# Fri3d_2024_Exp0_01.net
KiCad netlist of a schematic drawn in Altium Designer
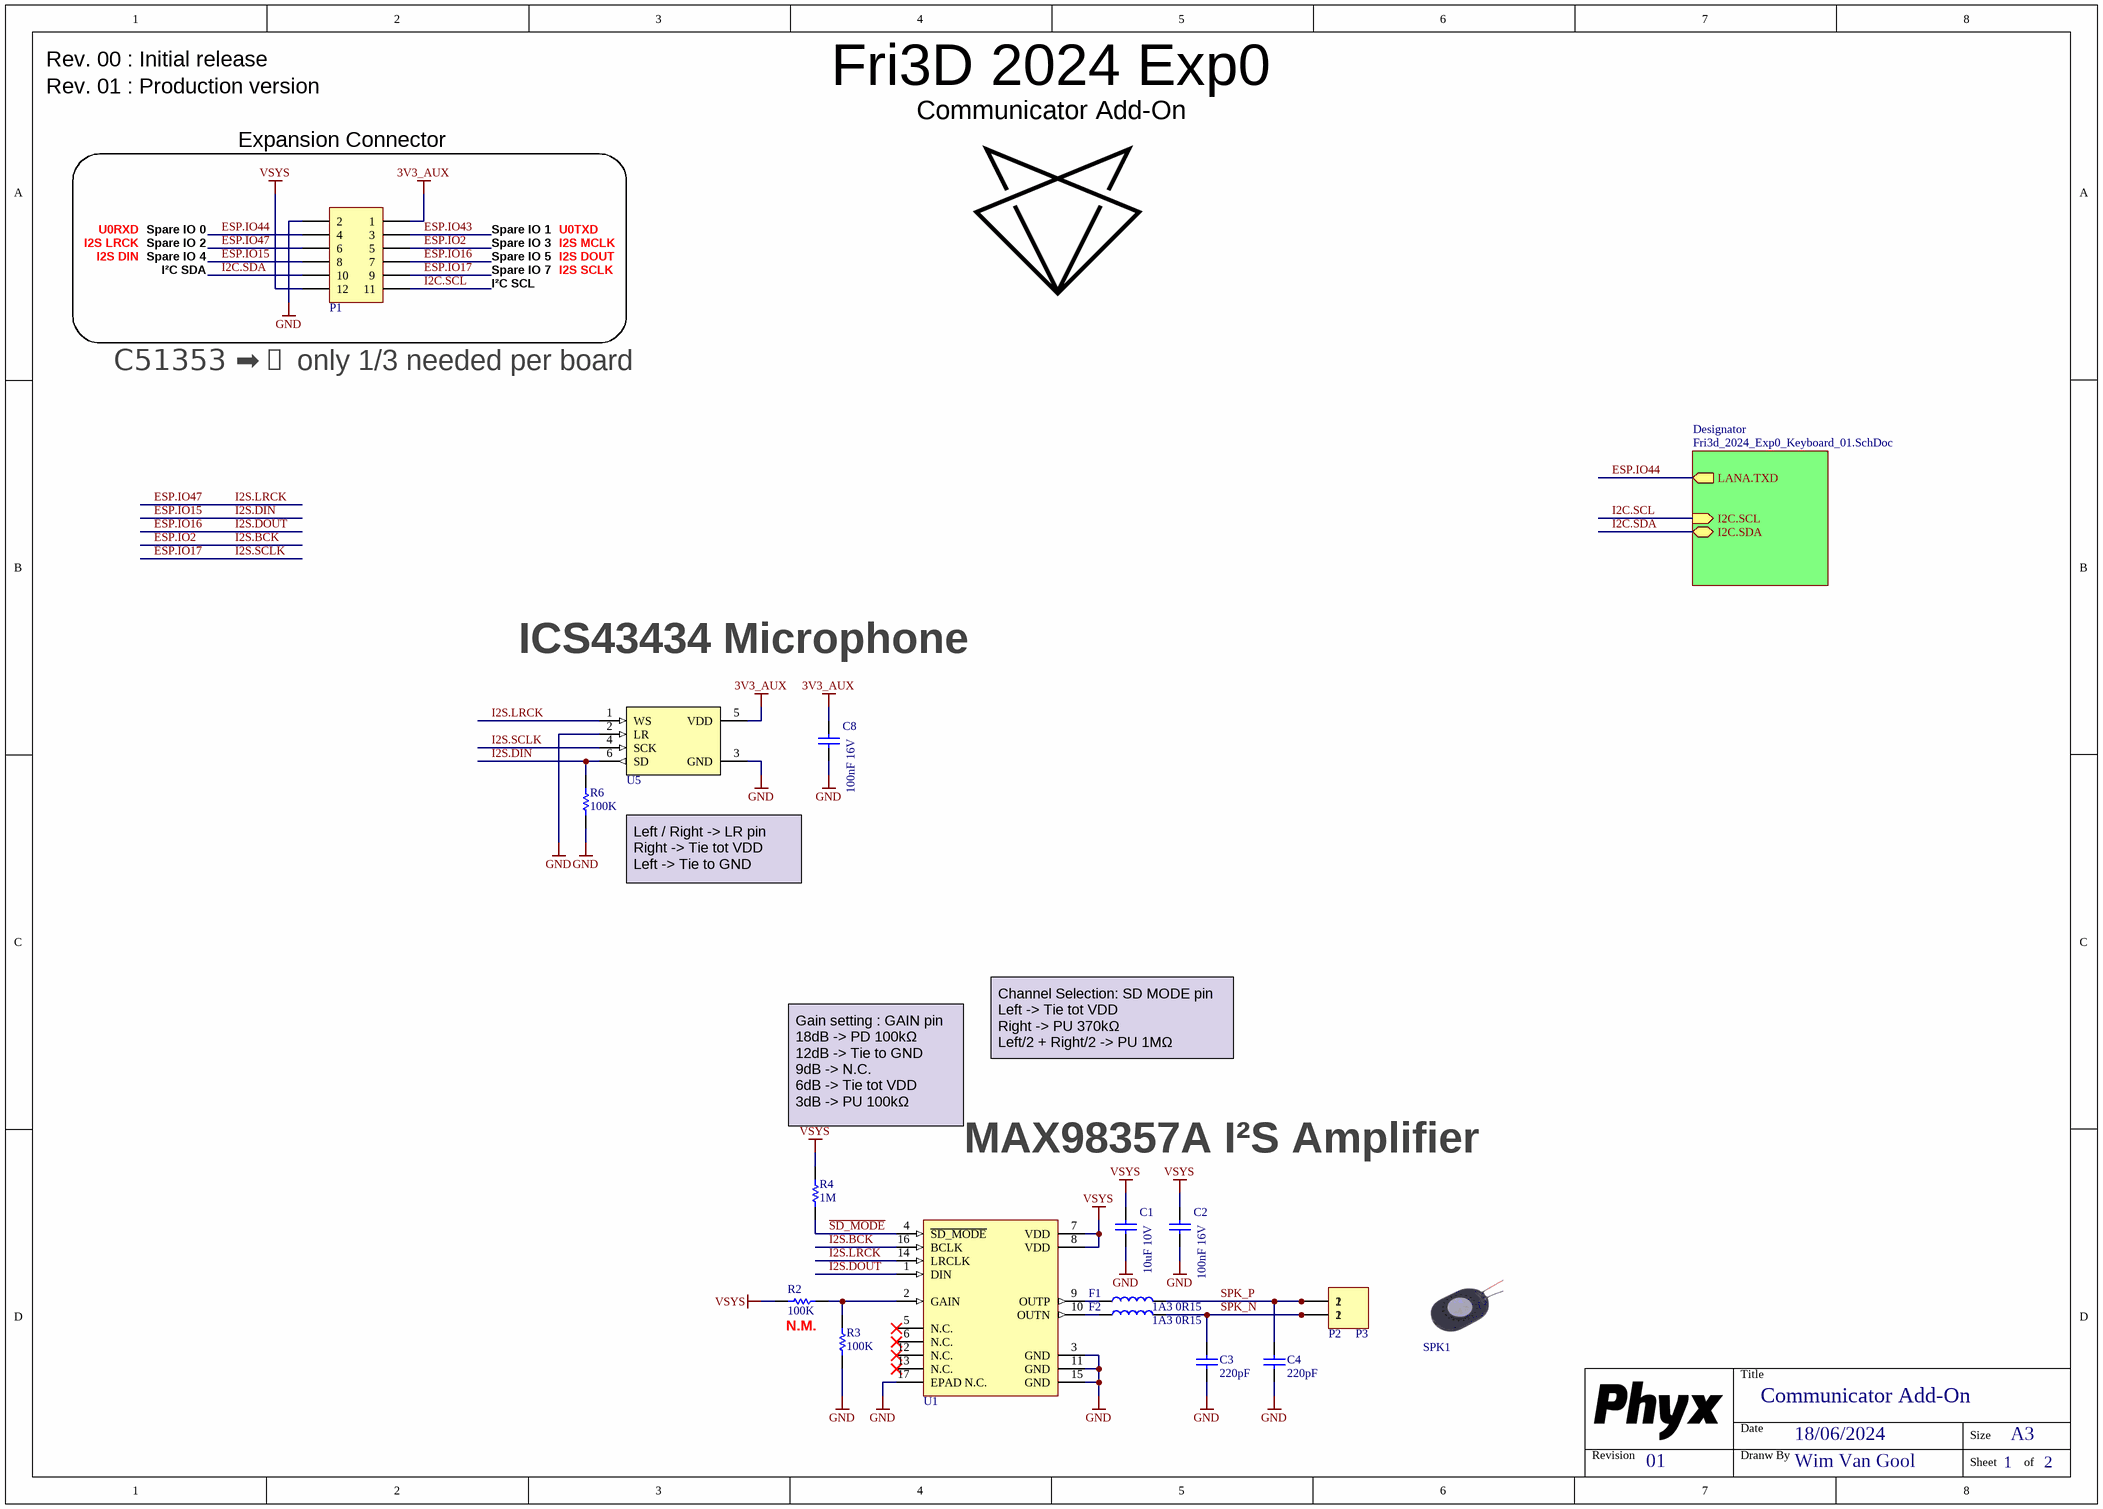
[diagram p0: Fri3d_2024_Exp0_01.SchDoc]

(export (version "E")
  (design (tool "Eeschema 10.0.6"))
  (components
    (comp (ref "C1")
      (value "10uF 10V")
      (footprint "C0805_N")
      (description "Capacitor Ceramic")
      (fields (field (name "Comment") "CAP_CERAMIC"))
      (libsource (lib "Phyx_Components") (part "CAP_CERAMIC"))
    )
    (comp (ref "C2")
      (value "100nF 16V")
      (footprint "C0603_N")
      (description "Capacitor Ceramic")
      (libsource (lib "Phyx_Components") (part "CAP_CERAMIC"))
    )
    (comp (ref "C3")
      (value "220pF")
      (footprint "C0603_N")
      (description "Capacitor Ceramic")
      (fields (field (name "Comment") "CAP_CERAMIC"))
      (libsource (lib "Phyx_Components") (part "CAP_CERAMIC"))
    )
    (comp (ref "C4")
      (value "220pF")
      (footprint "C0603_N")
      (description "Capacitor Ceramic")
      (fields (field (name "Comment") "CAP_CERAMIC"))
      (libsource (lib "Phyx_Components") (part "CAP_CERAMIC"))
    )
    (comp (ref "C8")
      (value "100nF 16V")
      (footprint "C0603_N")
      (description "Capacitor Ceramic")
      (libsource (lib "Phyx_Components") (part "CAP_CERAMIC"))
    )
    (comp (ref "F1")
      (value "1A3 0R15")
      (footprint "L0603")
      (fields (field (name "Comment") "BLM18KG601SN1D"))
      (libsource (lib "Phyx_Components") (part "FERRITE"))
    )
    (comp (ref "F2")
      (value "1A3 0R15")
      (footprint "L0603")
      (fields (field (name "Comment") "BLM18KG601SN1D"))
      (libsource (lib "Phyx_Components") (part "FERRITE"))
    )
    (comp (ref "P1")
      (value "Header 6X2")
      (footprint "HDR2X6")
      (libsource (lib "Phyx_Components") (part "Header 6X2"))
    )
    (comp (ref "P2")
      (value "Header 2.0mm Shrouded 2")
      (footprint "WE_620102131822")
      (libsource (lib "") (part "Header 2_1"))
    )
    (comp (ref "P3")
      (value "Header 2 RA")
      (footprint "HDR1X2_RA")
      (libsource (lib "Phyx_Components") (part "Header 2"))
    )
    (comp (ref "R2")
      (value "100K")
      (footprint "R0603_N")
      (fields (field (name "Comment") "RESISTOR"))
      (libsource (lib "Phyx_Components") (part "RESISTOR"))
    )
    (comp (ref "R3")
      (value "100K")
      (footprint "R0603_N")
      (fields (field (name "Comment") "RESISTOR"))
      (libsource (lib "Phyx_Components") (part "RESISTOR"))
    )
    (comp (ref "R4")
      (value "1M")
      (footprint "R0603_N")
      (fields (field (name "Comment") "RESISTOR"))
      (libsource (lib "Phyx_Components") (part "RESISTOR"))
    )
    (comp (ref "R6")
      (value "100K")
      (footprint "R0603_N")
      (fields (field (name "Comment") "RESISTOR"))
      (libsource (lib "Phyx_Components") (part "RESISTOR"))
    )
    (comp (ref "SPK1")
      (value "INGHAi GSPK3020035PN 8R 1W 100mm Leads")
      (description "SPEAKER 8R 1W 10cm")
      (libsource (lib "Phyx_Components") (part "GSPK3020035PN"))
    )
    (comp (ref "U1")
      (value "Mono I²S DAC AMP 3W 2.5~5.5V")
      (footprint "QFN_16_0.5_3X3")
      (description "=Description")
      (libsource (lib "Phyx_Components") (part "ADI_MAX98357_QFN"))
    )
    (comp (ref "U5")
      (value "I2S MIC ICS-43434")
      (footprint "TDK_ICS-43434")
      (description "=Description")
      (libsource (lib "Phyx_Components") (part "TDK_ICS-43434"))
    )
  )
  (nets
    (net (code "2") (name "/ESP.IO2") (class "Default")
      (node (ref "P1") (pin "5") (pinfunction "5_5") (pintype "passive"))
      (node (ref "U1") (pin "16") (pinfunction "BCLK_16") (pintype "input"))
    )
    (net (code "3") (name "/ESP.IO15") (class "Default")
      (node (ref "P1") (pin "8") (pinfunction "8_8") (pintype "passive"))
      (node (ref "R6") (pin "1") (pinfunction "1_1") (pintype "passive"))
      (node (ref "U5") (pin "6") (pinfunction "SD_6") (pintype "output"))
    )
    (net (code "4") (name "/ESP.IO16") (class "Default")
      (node (ref "P1") (pin "7") (pinfunction "7_7") (pintype "passive"))
      (node (ref "U1") (pin "1") (pinfunction "DIN_1") (pintype "input"))
    )
    (net (code "5") (name "/ESP.IO17") (class "Default")
      (node (ref "P1") (pin "9") (pinfunction "9_9") (pintype "passive"))
      (node (ref "U5") (pin "4") (pinfunction "SCK_4") (pintype "input"))
    )
    (net (code "6") (name "/ESP.IO43") (class "Default")
      (node (ref "P1") (pin "3") (pinfunction "3_3") (pintype "passive"))
    )
    (net (code "7") (name "/ESP.IO44") (class "Default")
      (node (ref "P1") (pin "4") (pinfunction "4_4") (pintype "passive"))
    )
    (net (code "8") (name "/ESP.IO47") (class "Default")
      (node (ref "P1") (pin "6") (pinfunction "6_6") (pintype "passive"))
      (node (ref "U1") (pin "14") (pinfunction "LRCLK_14") (pintype "input"))
      (node (ref "U5") (pin "1") (pinfunction "WS_1") (pintype "input"))
    )
    (net (code "9") (name "/I2C.SCL") (class "Default")
      (node (ref "P1") (pin "11") (pinfunction "11_11") (pintype "passive"))
    )
    (net (code "10") (name "/I2C.SDA") (class "Default")
      (node (ref "P1") (pin "10") (pinfunction "10_10") (pintype "passive"))
    )
    (net (code "11") (name "/SPK_N") (class "Default")
      (node (ref "C3") (pin "1") (pinfunction "1_1") (pintype "passive"))
      (node (ref "F2") (pin "2") (pinfunction "2_2") (pintype "passive"))
      (node (ref "P2") (pin "2") (pinfunction "2_2") (pintype "passive"))
      (node (ref "P3") (pin "1") (pinfunction "1_1") (pintype "passive"))
    )
    (net (code "12") (name "/SPK_P") (class "Default")
      (node (ref "C4") (pin "1") (pinfunction "1_1") (pintype "passive"))
      (node (ref "F1") (pin "2") (pinfunction "2_2") (pintype "passive"))
      (node (ref "P2") (pin "1") (pinfunction "1_1") (pintype "passive"))
      (node (ref "P3") (pin "2") (pinfunction "2_2") (pintype "passive"))
    )
    (net (code "13") (name "/~{SD_MODE}") (class "Default")
      (node (ref "R4") (pin "2") (pinfunction "2_2") (pintype "passive"))
      (node (ref "U1") (pin "4") (pinfunction "~{SD_MODE}_4") (pintype "input"))
    )
    (net (code "14") (name "3V3_AUX") (class "Default")
      (node (ref "C8") (pin "1") (pinfunction "1_1") (pintype "passive"))
      (node (ref "P1") (pin "1") (pinfunction "1_1") (pintype "passive"))
      (node (ref "U5") (pin "5") (pinfunction "VDD_5") (pintype "power_in"))
    )
    (net (code "15") (name "GND") (class "Default")
      (node (ref "C1") (pin "2") (pinfunction "2_2") (pintype "passive"))
      (node (ref "C2") (pin "2") (pinfunction "2_2") (pintype "passive"))
      (node (ref "C3") (pin "2") (pinfunction "2_2") (pintype "passive"))
      (node (ref "C4") (pin "2") (pinfunction "2_2") (pintype "passive"))
      (node (ref "C8") (pin "2") (pinfunction "2_2") (pintype "passive"))
      (node (ref "P1") (pin "2") (pinfunction "2_2") (pintype "passive"))
      (node (ref "R3") (pin "2") (pinfunction "2_2") (pintype "passive"))
      (node (ref "R6") (pin "2") (pinfunction "2_2") (pintype "passive"))
      (node (ref "U1") (pin "11") (pinfunction "GND_11") (pintype "power_in"))
      (node (ref "U1") (pin "15") (pinfunction "GND_15") (pintype "power_in"))
      (node (ref "U1") (pin "17") (pinfunction "EPAD_N.C._17") (pintype "passive"))
      (node (ref "U1") (pin "3") (pinfunction "GND_3") (pintype "power_in"))
      (node (ref "U5") (pin "2") (pinfunction "LR_2") (pintype "input"))
      (node (ref "U5") (pin "3") (pinfunction "GND_3") (pintype "passive"))
    )
    (net (code "16") (name "Net-(U1-GAIN)") (class "Default")
      (node (ref "R2") (pin "1") (pinfunction "1_1") (pintype "passive"))
      (node (ref "R3") (pin "1") (pinfunction "1_1") (pintype "passive"))
      (node (ref "U1") (pin "2") (pinfunction "GAIN_2") (pintype "input"))
    )
    (net (code "17") (name "Net-(U1-OUTN)") (class "Default")
      (node (ref "F2") (pin "1") (pinfunction "1_1") (pintype "passive"))
      (node (ref "U1") (pin "10") (pinfunction "OUTN_10") (pintype "output"))
    )
    (net (code "18") (name "Net-(U1-OUTP)") (class "Default")
      (node (ref "F1") (pin "1") (pinfunction "1_1") (pintype "passive"))
      (node (ref "U1") (pin "9") (pinfunction "OUTP_9") (pintype "output"))
    )
    (net (code "19") (name "VSYS") (class "Default")
      (node (ref "C1") (pin "1") (pinfunction "1_1") (pintype "passive"))
      (node (ref "C2") (pin "1") (pinfunction "1_1") (pintype "passive"))
      (node (ref "P1") (pin "12") (pinfunction "12_12") (pintype "passive"))
      (node (ref "R2") (pin "2") (pinfunction "2_2") (pintype "passive"))
      (node (ref "R4") (pin "1") (pinfunction "1_1") (pintype "passive"))
      (node (ref "U1") (pin "7") (pinfunction "VDD_7") (pintype "power_in"))
      (node (ref "U1") (pin "8") (pinfunction "VDD_8") (pintype "power_in"))
    )
    (net (code "20") (name "unconnected-(U1-N.C.-Pad5)") (class "Default")
      (node (ref "U1") (pin "5") (pinfunction "N.C._5") (pintype "passive+no_connect"))
    )
    (net (code "21") (name "unconnected-(U1-N.C.-Pad6)") (class "Default")
      (node (ref "U1") (pin "6") (pinfunction "N.C._6") (pintype "passive+no_connect"))
    )
    (net (code "22") (name "unconnected-(U1-N.C.-Pad12)") (class "Default")
      (node (ref "U1") (pin "12") (pinfunction "N.C._12") (pintype "passive+no_connect"))
    )
    (net (code "23") (name "unconnected-(U1-N.C.-Pad13)") (class "Default")
      (node (ref "U1") (pin "13") (pinfunction "N.C._13") (pintype "passive+no_connect"))
    )
  )
)
